# fbri_development.net
KiCad netlist of a schematic drawn in EAGLE
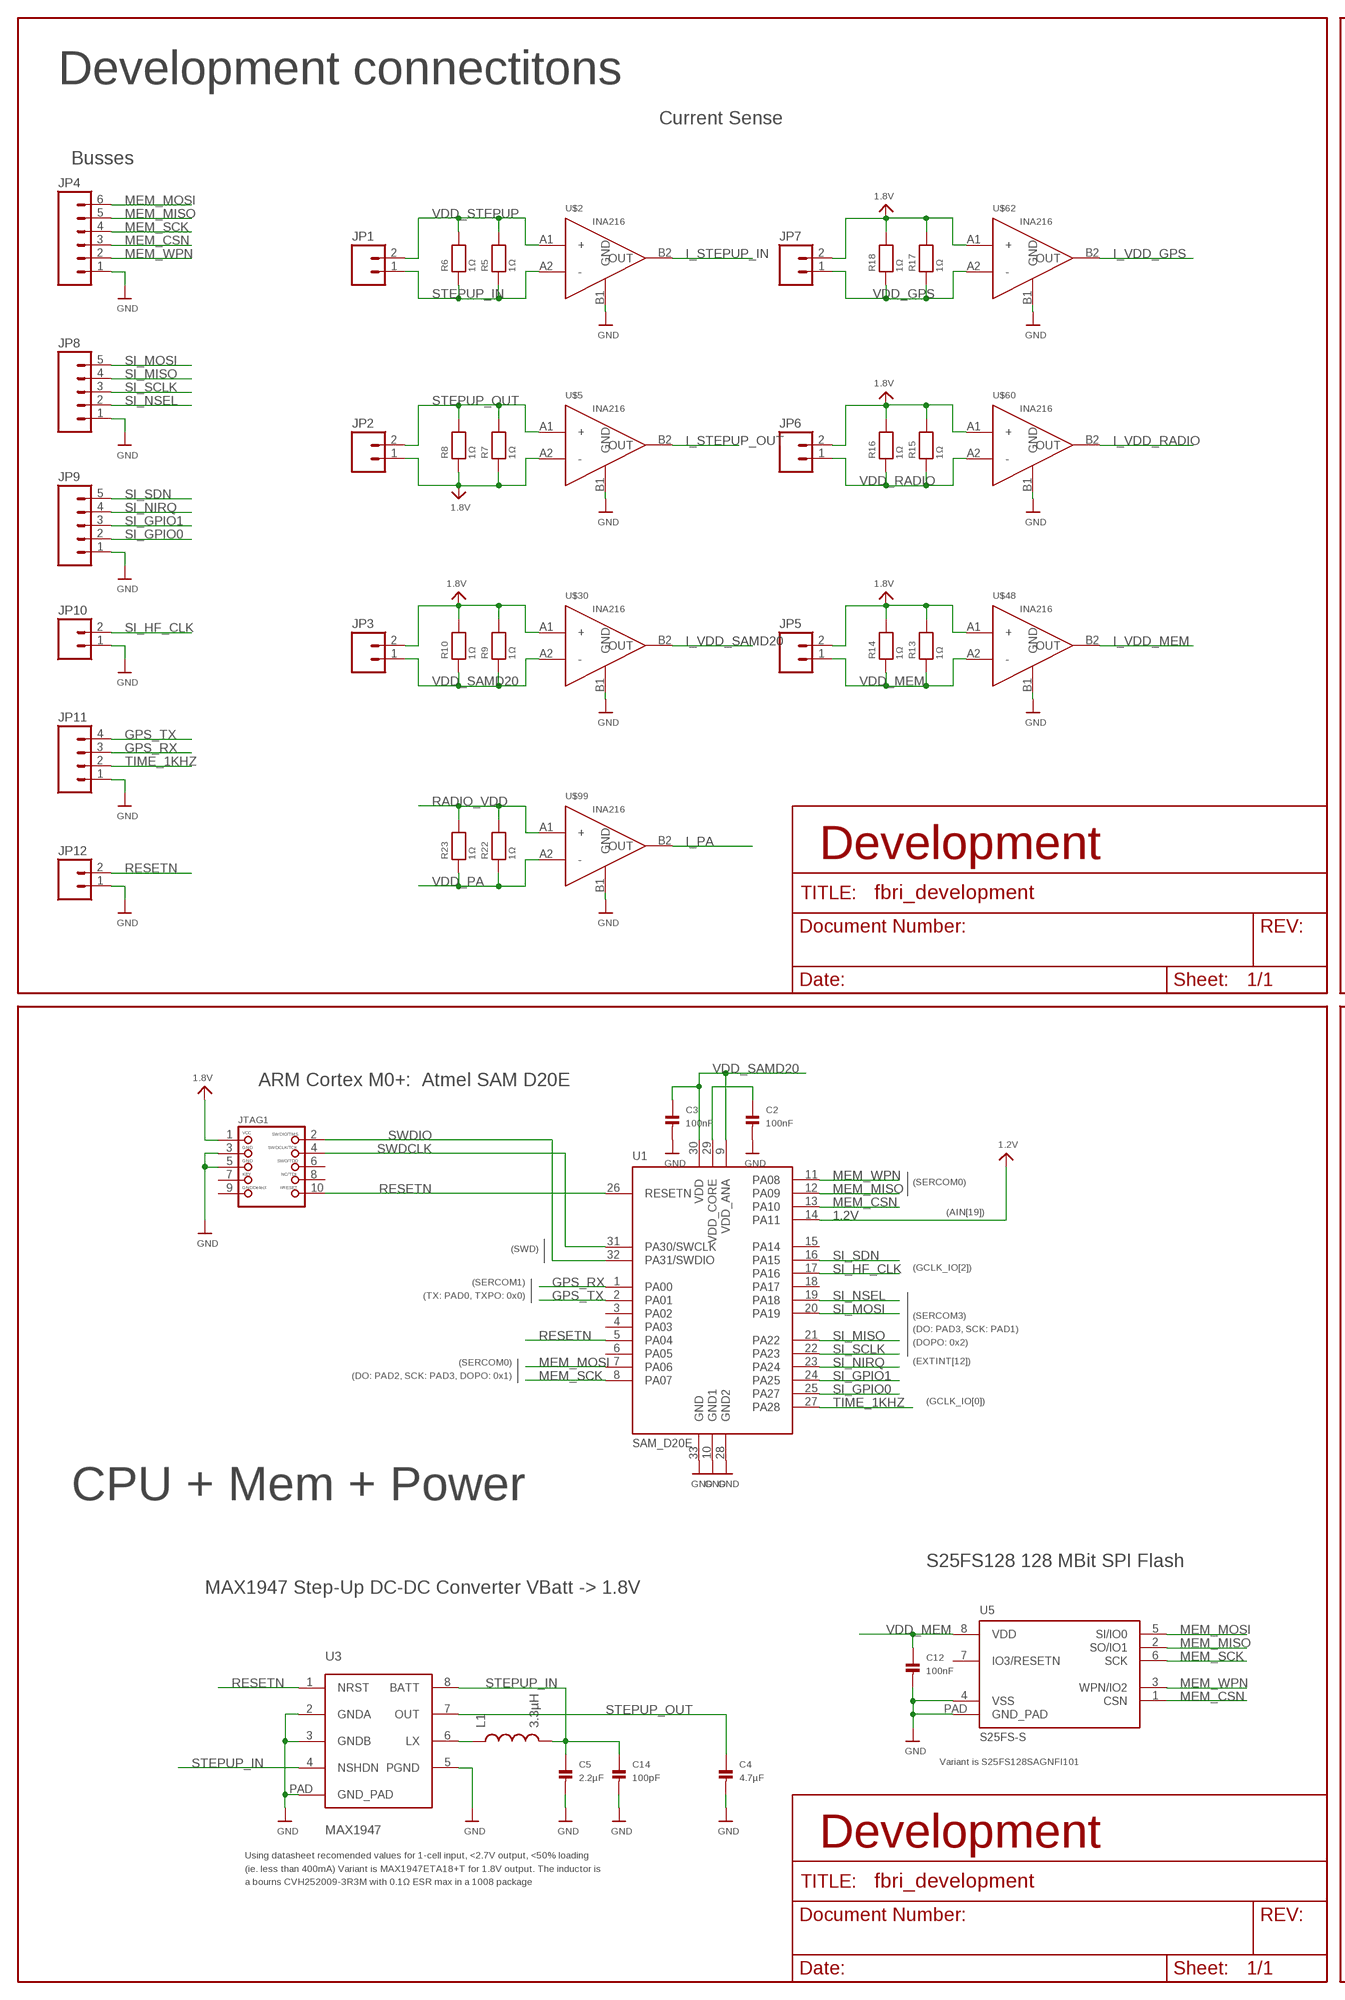
[diagram p0: schematic, sheet 1, part 1 of 2]
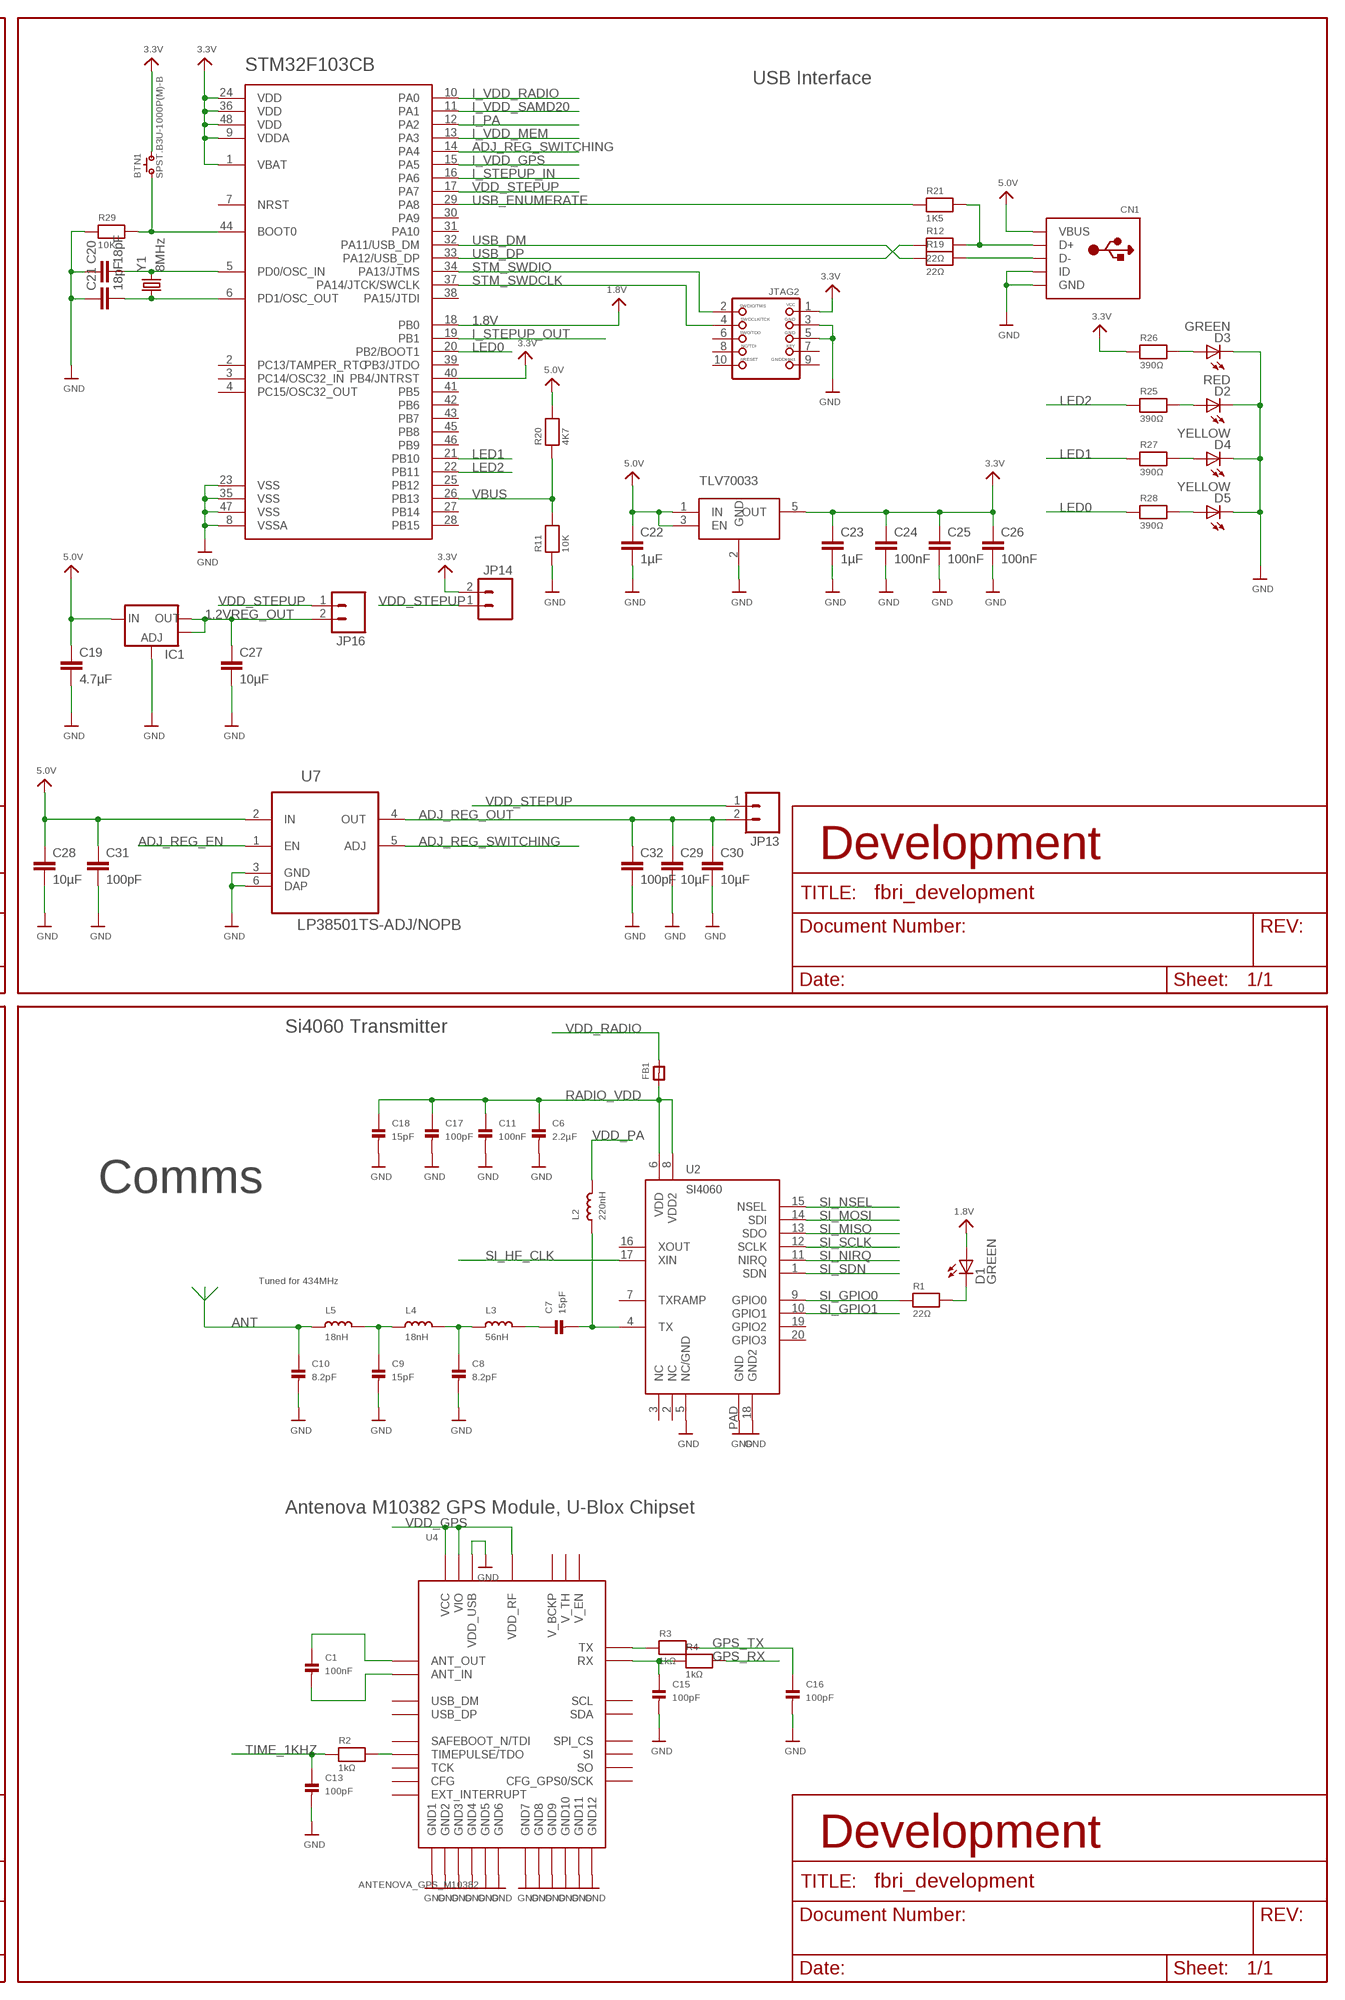
[diagram p1: schematic, sheet 1, part 2 of 2]

(export (version "E")
  (design (tool "Eeschema 10.0.6"))
  (components
    (comp (ref "BTN1")
      (value "SPST.B3U-1000P(M)-B")
      (footprint "eagle-import:B3U-1000P(M)-B")
      (libsource (lib "eagle-import") (part "SPST.B3U-1000P(M)-B"))
    )
    (comp (ref "C1")
      (value "100nF")
      (footprint "eagle-import:_0402")
      (libsource (lib "eagle-import") (part "CAP_CERAMIC_0402"))
    )
    (comp (ref "C2")
      (value "100nF")
      (footprint "eagle-import:_0402")
      (libsource (lib "eagle-import") (part "CAP_CERAMIC_0402"))
    )
    (comp (ref "C3")
      (value "100nF")
      (footprint "eagle-import:_0402")
      (libsource (lib "eagle-import") (part "CAP_CERAMIC_0402"))
    )
    (comp (ref "C4")
      (value "4.7µF")
      (footprint "eagle-import:_0402")
      (libsource (lib "eagle-import") (part "CAP_CERAMIC_0402"))
    )
    (comp (ref "C5")
      (value "2.2µF")
      (footprint "eagle-import:_0402")
      (libsource (lib "eagle-import") (part "CAP_CERAMIC_0402"))
    )
    (comp (ref "C6")
      (value "2.2µF")
      (footprint "eagle-import:_0402")
      (libsource (lib "eagle-import") (part "CAP_CERAMIC_0402"))
    )
    (comp (ref "C7")
      (value "15pF")
      (footprint "eagle-import:_0402")
      (libsource (lib "eagle-import") (part "CAP_CERAMIC_0402"))
    )
    (comp (ref "C8")
      (value "8.2pF")
      (footprint "eagle-import:_0402")
      (libsource (lib "eagle-import") (part "CAP_CERAMIC_0402"))
    )
    (comp (ref "C9")
      (value "15pF")
      (footprint "eagle-import:_0402")
      (libsource (lib "eagle-import") (part "CAP_CERAMIC_0402"))
    )
    (comp (ref "C10")
      (value "8.2pF")
      (footprint "eagle-import:_0402")
      (libsource (lib "eagle-import") (part "CAP_CERAMIC_0402"))
    )
    (comp (ref "C11")
      (value "100nF")
      (footprint "eagle-import:_0402")
      (libsource (lib "eagle-import") (part "CAP_CERAMIC_0402"))
    )
    (comp (ref "C12")
      (value "100nF")
      (footprint "eagle-import:_0402")
      (libsource (lib "eagle-import") (part "CAP_CERAMIC_0402"))
    )
    (comp (ref "C13")
      (value "100pF")
      (footprint "eagle-import:_0402")
      (libsource (lib "eagle-import") (part "CAP_CERAMIC_0402"))
    )
    (comp (ref "C14")
      (value "100pF")
      (footprint "eagle-import:_0402")
      (libsource (lib "eagle-import") (part "CAP_CERAMIC_0402"))
    )
    (comp (ref "C15")
      (value "100pF")
      (footprint "eagle-import:_0402")
      (libsource (lib "eagle-import") (part "CAP_CERAMIC_0402"))
    )
    (comp (ref "C16")
      (value "100pF")
      (footprint "eagle-import:_0402")
      (libsource (lib "eagle-import") (part "CAP_CERAMIC_0402"))
    )
    (comp (ref "C17")
      (value "100pF")
      (footprint "eagle-import:_0402")
      (libsource (lib "eagle-import") (part "CAP_CERAMIC_0402"))
    )
    (comp (ref "C18")
      (value "15pF")
      (footprint "eagle-import:_0402")
      (libsource (lib "eagle-import") (part "CAP_CERAMIC_0402"))
    )
    (comp (ref "C19")
      (value "4.7µF")
      (footprint "eagle-import:C0603K")
      (libsource (lib "eagle-import") (part "C-EUC0603K"))
    )
    (comp (ref "C20")
      (value "18pF")
      (footprint "eagle-import:C0603K")
      (libsource (lib "eagle-import") (part "C-EUC0603K"))
    )
    (comp (ref "C21")
      (value "18pF")
      (footprint "eagle-import:C0603K")
      (libsource (lib "eagle-import") (part "C-EUC0603K"))
    )
    (comp (ref "C22")
      (value "1µF")
      (footprint "eagle-import:C0603K")
      (libsource (lib "eagle-import") (part "C-EUC0603K"))
    )
    (comp (ref "C23")
      (value "1µF")
      (footprint "eagle-import:C0603K")
      (libsource (lib "eagle-import") (part "C-EUC0603K"))
    )
    (comp (ref "C24")
      (value "100nF")
      (footprint "eagle-import:C0603K")
      (libsource (lib "eagle-import") (part "C-EUC0603K"))
    )
    (comp (ref "C25")
      (value "100nF")
      (footprint "eagle-import:C0603K")
      (libsource (lib "eagle-import") (part "C-EUC0603K"))
    )
    (comp (ref "C26")
      (value "100nF")
      (footprint "eagle-import:C0603K")
      (libsource (lib "eagle-import") (part "C-EUC0603K"))
    )
    (comp (ref "C27")
      (value "10µF")
      (footprint "eagle-import:C0603K")
      (libsource (lib "eagle-import") (part "C-EUC0603K"))
    )
    (comp (ref "C28")
      (value "10µF")
      (footprint "eagle-import:C0603K")
      (libsource (lib "eagle-import") (part "C-EUC0603K"))
    )
    (comp (ref "C29")
      (value "10µF")
      (footprint "eagle-import:C0603K")
      (libsource (lib "eagle-import") (part "C-EUC0603K"))
    )
    (comp (ref "C30")
      (value "10µF")
      (footprint "eagle-import:C0603K")
      (libsource (lib "eagle-import") (part "C-EUC0603K"))
    )
    (comp (ref "C31")
      (value "100pF")
      (footprint "eagle-import:C0603K")
      (libsource (lib "eagle-import") (part "C-EUC0603K"))
    )
    (comp (ref "C32")
      (value "100pF")
      (footprint "eagle-import:C0603K")
      (libsource (lib "eagle-import") (part "C-EUC0603K"))
    )
    (comp (ref "CN1")
      (value "USBMINIB")
      (footprint "eagle-import:USB-MINIB")
      (libsource (lib "eagle-import") (part "USBMINIB"))
    )
    (comp (ref "D1")
      (value "GREEN")
      (footprint "eagle-import:CHIPLED_0603")
      (libsource (lib "eagle-import") (part "LEDCHIPLED_0603"))
    )
    (comp (ref "D2")
      (value "RED")
      (footprint "eagle-import:CHIPLED_0603")
      (libsource (lib "eagle-import") (part "LEDCHIPLED_0603"))
    )
    (comp (ref "D3")
      (value "GREEN")
      (footprint "eagle-import:CHIPLED_0603")
      (libsource (lib "eagle-import") (part "LEDCHIPLED_0603"))
    )
    (comp (ref "D4")
      (value "YELLOW")
      (footprint "eagle-import:CHIPLED_0603")
      (libsource (lib "eagle-import") (part "LEDCHIPLED_0603"))
    )
    (comp (ref "D5")
      (value "YELLOW")
      (footprint "eagle-import:CHIPLED_0603")
      (libsource (lib "eagle-import") (part "LEDCHIPLED_0603"))
    )
    (comp (ref "FB1")
      (value "FERRITE_0402")
      (footprint "eagle-import:_0402")
      (libsource (lib "eagle-import") (part "FERRITE_0402"))
    )
    (comp (ref "IC1")
      (value "V_REG_LM1117SOT223")
      (footprint "eagle-import:SOT223")
      (libsource (lib "eagle-import") (part "V_REG_LM1117SOT223"))
    )
    (comp (ref "IC3")
      (value "TLV70033DCK")
      (footprint "eagle-import:SC70-5L")
      (libsource (lib "eagle-import") (part "TLV700DCK"))
    )
    (comp (ref "JP1")
      (value "M02LOCK")
      (footprint "eagle-import:1X02_LOCK")
      (libsource (lib "eagle-import") (part "M02LOCK"))
    )
    (comp (ref "JP2")
      (value "M02LOCK")
      (footprint "eagle-import:1X02_LOCK")
      (libsource (lib "eagle-import") (part "M02LOCK"))
    )
    (comp (ref "JP3")
      (value "M02LOCK")
      (footprint "eagle-import:1X02_LOCK")
      (libsource (lib "eagle-import") (part "M02LOCK"))
    )
    (comp (ref "JP4")
      (value "M06LOCK")
      (footprint "eagle-import:1X06_LOCK")
      (libsource (lib "eagle-import") (part "M06LOCK"))
    )
    (comp (ref "JP5")
      (value "M02LOCK")
      (footprint "eagle-import:1X02_LOCK")
      (libsource (lib "eagle-import") (part "M02LOCK"))
    )
    (comp (ref "JP6")
      (value "M02LOCK")
      (footprint "eagle-import:1X02_LOCK")
      (libsource (lib "eagle-import") (part "M02LOCK"))
    )
    (comp (ref "JP7")
      (value "M02LOCK")
      (footprint "eagle-import:1X02_LOCK")
      (libsource (lib "eagle-import") (part "M02LOCK"))
    )
    (comp (ref "JP8")
      (value "M05LOCK")
      (footprint "eagle-import:1X05_LOCK")
      (libsource (lib "eagle-import") (part "M05LOCK"))
    )
    (comp (ref "JP9")
      (value "M05LOCK")
      (footprint "eagle-import:1X05_LOCK")
      (libsource (lib "eagle-import") (part "M05LOCK"))
    )
    (comp (ref "JP10")
      (value "M02LOCK")
      (footprint "eagle-import:1X02_LOCK")
      (libsource (lib "eagle-import") (part "M02LOCK"))
    )
    (comp (ref "JP11")
      (value "M04LOCK")
      (footprint "eagle-import:1X04_LOCK")
      (libsource (lib "eagle-import") (part "M04LOCK"))
    )
    (comp (ref "JP12")
      (value "M02LOCK")
      (footprint "eagle-import:1X02_LOCK")
      (libsource (lib "eagle-import") (part "M02LOCK"))
    )
    (comp (ref "JP13")
      (value "M02LOCK")
      (footprint "eagle-import:1X02_LOCK")
      (libsource (lib "eagle-import") (part "M02LOCK"))
    )
    (comp (ref "JP14")
      (value "M02LOCK")
      (footprint "eagle-import:1X02_LOCK")
      (libsource (lib "eagle-import") (part "M02LOCK"))
    )
    (comp (ref "JP16")
      (value "M02LOCK")
      (footprint "eagle-import:1X02_LOCK")
      (libsource (lib "eagle-import") (part "M02LOCK"))
    )
    (comp (ref "JTAG1")
      (value "JTAG-CORTEXM3SMT")
      (footprint "eagle-import:2X05_1.27MM_SMT")
      (libsource (lib "eagle-import") (part "JTAG-CORTEXM3SMT"))
    )
    (comp (ref "JTAG2")
      (value "JTAG-CORTEXM3SMT")
      (footprint "eagle-import:2X05_1.27MM_SMT")
      (libsource (lib "eagle-import") (part "JTAG-CORTEXM3SMT"))
    )
    (comp (ref "L1")
      (value "3.3µH")
      (footprint "eagle-import:1007")
      (libsource (lib "eagle-import") (part "INDUCTOR1007"))
    )
    (comp (ref "L2")
      (value "220nH")
      (footprint "eagle-import:_0402")
      (libsource (lib "eagle-import") (part "INDUCTOR_0402"))
    )
    (comp (ref "L3")
      (value "56nH")
      (footprint "eagle-import:_0402")
      (libsource (lib "eagle-import") (part "INDUCTOR_0402"))
    )
    (comp (ref "L4")
      (value "18nH")
      (footprint "eagle-import:_0402")
      (libsource (lib "eagle-import") (part "INDUCTOR_0402"))
    )
    (comp (ref "L5")
      (value "18nH")
      (footprint "eagle-import:_0402")
      (libsource (lib "eagle-import") (part "INDUCTOR_0402"))
    )
    (comp (ref "R1")
      (value "22Ω")
      (footprint "eagle-import:_0402")
      (libsource (lib "eagle-import") (part "RESISTOR_0402"))
    )
    (comp (ref "R2")
      (value "1kΩ")
      (footprint "eagle-import:_0402")
      (libsource (lib "eagle-import") (part "RESISTOR_0402"))
    )
    (comp (ref "R3")
      (value "1kΩ")
      (footprint "eagle-import:_0402")
      (libsource (lib "eagle-import") (part "RESISTOR_0402"))
    )
    (comp (ref "R4")
      (value "1kΩ")
      (footprint "eagle-import:_0402")
      (libsource (lib "eagle-import") (part "RESISTOR_0402"))
    )
    (comp (ref "R5")
      (value "1Ω")
      (footprint "eagle-import:_0402")
      (libsource (lib "eagle-import") (part "RESISTOR_0402"))
    )
    (comp (ref "R6")
      (value "1Ω")
      (footprint "eagle-import:_0402")
      (libsource (lib "eagle-import") (part "RESISTOR_0402"))
    )
    (comp (ref "R7")
      (value "1Ω")
      (footprint "eagle-import:_0402")
      (libsource (lib "eagle-import") (part "RESISTOR_0402"))
    )
    (comp (ref "R8")
      (value "1Ω")
      (footprint "eagle-import:_0402")
      (libsource (lib "eagle-import") (part "RESISTOR_0402"))
    )
    (comp (ref "R9")
      (value "1Ω")
      (footprint "eagle-import:_0402")
      (libsource (lib "eagle-import") (part "RESISTOR_0402"))
    )
    (comp (ref "R10")
      (value "1Ω")
      (footprint "eagle-import:_0402")
      (libsource (lib "eagle-import") (part "RESISTOR_0402"))
    )
    (comp (ref "R11")
      (value "10K")
      (footprint "eagle-import:0603-MINI")
      (libsource (lib "eagle-import") (part "RESISTOR0603MINI"))
    )
    (comp (ref "R12")
      (value "22Ω")
      (footprint "eagle-import:0603-MINI")
      (libsource (lib "eagle-import") (part "RESISTOR0603MINI"))
    )
    (comp (ref "R13")
      (value "1Ω")
      (footprint "eagle-import:_0402")
      (libsource (lib "eagle-import") (part "RESISTOR_0402"))
    )
    (comp (ref "R14")
      (value "1Ω")
      (footprint "eagle-import:_0402")
      (libsource (lib "eagle-import") (part "RESISTOR_0402"))
    )
    (comp (ref "R15")
      (value "1Ω")
      (footprint "eagle-import:_0402")
      (libsource (lib "eagle-import") (part "RESISTOR_0402"))
    )
    (comp (ref "R16")
      (value "1Ω")
      (footprint "eagle-import:_0402")
      (libsource (lib "eagle-import") (part "RESISTOR_0402"))
    )
    (comp (ref "R17")
      (value "1Ω")
      (footprint "eagle-import:_0402")
      (libsource (lib "eagle-import") (part "RESISTOR_0402"))
    )
    (comp (ref "R18")
      (value "1Ω")
      (footprint "eagle-import:_0402")
      (libsource (lib "eagle-import") (part "RESISTOR_0402"))
    )
    (comp (ref "R19")
      (value "22Ω")
      (footprint "eagle-import:0603-MINI")
      (libsource (lib "eagle-import") (part "RESISTOR0603MINI"))
    )
    (comp (ref "R20")
      (value "4K7")
      (footprint "eagle-import:0603-MINI")
      (libsource (lib "eagle-import") (part "RESISTOR0603MINI"))
    )
    (comp (ref "R21")
      (value "1K5")
      (footprint "eagle-import:0603-MINI")
      (libsource (lib "eagle-import") (part "RESISTOR0603MINI"))
    )
    (comp (ref "R22")
      (value "1Ω")
      (footprint "eagle-import:_0402")
      (libsource (lib "eagle-import") (part "RESISTOR_0402"))
    )
    (comp (ref "R23")
      (value "1Ω")
      (footprint "eagle-import:_0402")
      (libsource (lib "eagle-import") (part "RESISTOR_0402"))
    )
    (comp (ref "R25")
      (value "390Ω")
      (footprint "eagle-import:0603-MINI")
      (libsource (lib "eagle-import") (part "RESISTOR0603MINI"))
    )
    (comp (ref "R26")
      (value "390Ω")
      (footprint "eagle-import:0603-MINI")
      (libsource (lib "eagle-import") (part "RESISTOR0603MINI"))
    )
    (comp (ref "R27")
      (value "390Ω")
      (footprint "eagle-import:0603-MINI")
      (libsource (lib "eagle-import") (part "RESISTOR0603MINI"))
    )
    (comp (ref "R28")
      (value "390Ω")
      (footprint "eagle-import:0603-MINI")
      (libsource (lib "eagle-import") (part "RESISTOR0603MINI"))
    )
    (comp (ref "R29")
      (value "10K")
      (footprint "eagle-import:0603-MINI")
      (libsource (lib "eagle-import") (part "RESISTOR0603MINI"))
    )
    (comp (ref "U$2")
      (value "INA216")
      (footprint "eagle-import:WCSP-4")
      (libsource (lib "eagle-import") (part "INA216"))
    )
    (comp (ref "U$5")
      (value "INA216")
      (footprint "eagle-import:WCSP-4")
      (libsource (lib "eagle-import") (part "INA216"))
    )
    (comp (ref "U$30")
      (value "INA216")
      (footprint "eagle-import:WCSP-4")
      (libsource (lib "eagle-import") (part "INA216"))
    )
    (comp (ref "U$48")
      (value "INA216")
      (footprint "eagle-import:WCSP-4")
      (libsource (lib "eagle-import") (part "INA216"))
    )
    (comp (ref "U$60")
      (value "INA216")
      (footprint "eagle-import:WCSP-4")
      (libsource (lib "eagle-import") (part "INA216"))
    )
    (comp (ref "U$62")
      (value "INA216")
      (footprint "eagle-import:WCSP-4")
      (libsource (lib "eagle-import") (part "INA216"))
    )
    (comp (ref "U$99")
      (value "INA216")
      (footprint "eagle-import:WCSP-4")
      (libsource (lib "eagle-import") (part "INA216"))
    )
    (comp (ref "U1")
      (value "SAM_D20E")
      (footprint "eagle-import:QFN32_5MM")
      (libsource (lib "eagle-import") (part "SAM_D20E"))
    )
    (comp (ref "U2")
      (value "SI4060")
      (footprint "eagle-import:QFN20")
      (libsource (lib "eagle-import") (part "SI4060"))
    )
    (comp (ref "U3")
      (value "MAX1947")
      (footprint "eagle-import:TDFN8")
      (libsource (lib "eagle-import") (part "MAX1947"))
    )
    (comp (ref "U4")
      (value "ANTENOVA_GPS_M10382")
      (footprint "eagle-import:ANTENOVA_GPS_M10382")
      (libsource (lib "eagle-import") (part "ANTENOVA_GPS_M10382"))
    )
    (comp (ref "U5")
      (value "S25FS-S")
      (footprint "eagle-import:WSON8")
      (libsource (lib "eagle-import") (part "S25FS-S"))
    )
    (comp (ref "U6")
      (value "STM32F_48PIN")
      (footprint "eagle-import:TQFP48")
      (libsource (lib "eagle-import") (part "STM32F_48PIN"))
    )
    (comp (ref "U7")
      (value "LP38501TS-ADJ/NOPB")
      (footprint "eagle-import:TO170P1435X457-6N")
      (libsource (lib "eagle-import") (part "LP38501TS-ADJ/NOPB"))
    )
    (comp (ref "Y1")
      (value "8MHz")
      (footprint "eagle-import:CRYSTAL-SMD-5X3")
      (libsource (lib "eagle-import") (part "CRYSTAL5X3"))
    )
  )
  (nets
    (net (code "1") (name "/1.2VREG_OUT") (class "Default")
      (node (ref "C27") (pin "1") (pinfunction "1_1") (pintype "passive"))
      (node (ref "IC1") (pin "2") (pinfunction "OUT_2") (pintype "output"))
      (node (ref "IC1") (pin "4") (pinfunction "OUT_4") (pintype "output"))
      (node (ref "JP16") (pin "2") (pinfunction "2_2") (pintype "passive"))
    )
    (net (code "2") (name "/ADJ_REG_EN") (class "Default")
      (node (ref "U7") (pin "1") (pinfunction "EN_1") (pintype "input"))
    )
    (net (code "3") (name "/ADJ_REG_OUT") (class "Default")
      (node (ref "C29") (pin "1") (pinfunction "1_1") (pintype "passive"))
      (node (ref "C30") (pin "1") (pinfunction "1_1") (pintype "passive"))
      (node (ref "C32") (pin "1") (pinfunction "1_1") (pintype "passive"))
      (node (ref "JP13") (pin "2") (pinfunction "2_2") (pintype "passive"))
      (node (ref "U7") (pin "4") (pinfunction "OUT_4") (pintype "output"))
    )
    (net (code "4") (name "/ADJ_REG_SWITCHING") (class "Default")
      (node (ref "U6") (pin "14") (pinfunction "PA4_14") (pintype "bidirectional"))
      (node (ref "U7") (pin "5") (pinfunction "ADJ_5") (pintype "input"))
    )
    (net (code "5") (name "/ANT") (class "Default")
      (node (ref "C10") (pin "1") (pinfunction "P$1_1") (pintype "passive"))
      (node (ref "L5") (pin "1") (pinfunction "1_1") (pintype "passive"))
    )
    (net (code "6") (name "/GPS_RX") (class "Default")
      (node (ref "JP11") (pin "3") (pinfunction "3_3") (pintype "passive"))
      (node (ref "R4") (pin "2") (pinfunction "2_2") (pintype "passive"))
      (node (ref "U1") (pin "1") (pinfunction "PA00_1") (pintype "bidirectional"))
    )
    (net (code "7") (name "/GPS_TX") (class "Default")
      (node (ref "C16") (pin "1") (pinfunction "P$1_1") (pintype "passive"))
      (node (ref "JP11") (pin "4") (pinfunction "4_4") (pintype "passive"))
      (node (ref "R3") (pin "2") (pinfunction "2_2") (pintype "passive"))
      (node (ref "U1") (pin "2") (pinfunction "PA01_2") (pintype "bidirectional"))
    )
    (net (code "8") (name "/I_PA") (class "Default")
      (node (ref "U$99") (pin "B2") (pinfunction "OUT_B2") (pintype "bidirectional"))
      (node (ref "U6") (pin "12") (pinfunction "PA2_12") (pintype "bidirectional"))
    )
    (net (code "9") (name "/I_STEPUP_IN") (class "Default")
      (node (ref "U$2") (pin "B2") (pinfunction "OUT_B2") (pintype "bidirectional"))
      (node (ref "U6") (pin "16") (pinfunction "PA6_16") (pintype "bidirectional"))
    )
    (net (code "10") (name "/I_STEPUP_OUT") (class "Default")
      (node (ref "U$5") (pin "B2") (pinfunction "OUT_B2") (pintype "bidirectional"))
      (node (ref "U6") (pin "19") (pinfunction "PB1_19") (pintype "bidirectional"))
    )
    (net (code "11") (name "/I_VDD_GPS") (class "Default")
      (node (ref "U$62") (pin "B2") (pinfunction "OUT_B2") (pintype "bidirectional"))
      (node (ref "U6") (pin "15") (pinfunction "PA5_15") (pintype "bidirectional"))
    )
    (net (code "12") (name "/I_VDD_MEM") (class "Default")
      (node (ref "U$48") (pin "B2") (pinfunction "OUT_B2") (pintype "bidirectional"))
      (node (ref "U6") (pin "13") (pinfunction "PA3_13") (pintype "bidirectional"))
    )
    (net (code "13") (name "/I_VDD_RADIO") (class "Default")
      (node (ref "U$60") (pin "B2") (pinfunction "OUT_B2") (pintype "bidirectional"))
      (node (ref "U6") (pin "10") (pinfunction "PA0_10") (pintype "bidirectional"))
    )
    (net (code "14") (name "/I_VDD_SAMD20") (class "Default")
      (node (ref "U$30") (pin "B2") (pinfunction "OUT_B2") (pintype "bidirectional"))
      (node (ref "U6") (pin "11") (pinfunction "PA1_11") (pintype "bidirectional"))
    )
    (net (code "15") (name "/LED0") (class "Default")
      (node (ref "R28") (pin "1") (pinfunction "1_1") (pintype "passive"))
      (node (ref "U6") (pin "20") (pinfunction "PB2/BOOT1_20") (pintype "bidirectional"))
    )
    (net (code "16") (name "/LED1") (class "Default")
      (node (ref "R27") (pin "1") (pinfunction "1_1") (pintype "passive"))
      (node (ref "U6") (pin "21") (pinfunction "PB10_21") (pintype "bidirectional"))
    )
    (net (code "17") (name "/LED2") (class "Default")
      (node (ref "R25") (pin "1") (pinfunction "1_1") (pintype "passive"))
      (node (ref "U6") (pin "22") (pinfunction "PB11_22") (pintype "bidirectional"))
    )
    (net (code "18") (name "/MEM_CSN") (class "Default")
      (node (ref "JP4") (pin "3") (pinfunction "3_3") (pintype "passive"))
      (node (ref "U1") (pin "13") (pinfunction "PA10_13") (pintype "bidirectional"))
      (node (ref "U5") (pin "1") (pinfunction "CSN_1") (pintype "input"))
    )
    (net (code "19") (name "/MEM_MISO") (class "Default")
      (node (ref "JP4") (pin "5") (pinfunction "5_5") (pintype "passive"))
      (node (ref "U1") (pin "12") (pinfunction "PA09_12") (pintype "bidirectional"))
      (node (ref "U5") (pin "2") (pinfunction "SO/IO1_2") (pintype "output"))
    )
    (net (code "20") (name "/MEM_MOSI") (class "Default")
      (node (ref "JP4") (pin "6") (pinfunction "6_6") (pintype "passive"))
      (node (ref "U1") (pin "7") (pinfunction "PA06_7") (pintype "bidirectional"))
      (node (ref "U5") (pin "5") (pinfunction "SI/IO0_5") (pintype "bidirectional"))
    )
    (net (code "21") (name "/MEM_SCK") (class "Default")
      (node (ref "JP4") (pin "4") (pinfunction "4_4") (pintype "passive"))
      (node (ref "U1") (pin "8") (pinfunction "PA07_8") (pintype "bidirectional"))
      (node (ref "U5") (pin "6") (pinfunction "SCK_6") (pintype "input"))
    )
    (net (code "22") (name "/MEM_WPN") (class "Default")
      (node (ref "JP4") (pin "2") (pinfunction "2_2") (pintype "passive"))
      (node (ref "U1") (pin "11") (pinfunction "PA08_11") (pintype "bidirectional"))
      (node (ref "U5") (pin "3") (pinfunction "WPN/IO2_3") (pintype "output"))
    )
    (net (code "23") (name "/RADIO_VDD") (class "Default")
      (node (ref "C11") (pin "1") (pinfunction "P$1_1") (pintype "passive"))
      (node (ref "C17") (pin "1") (pinfunction "P$1_1") (pintype "passive"))
      (node (ref "C18") (pin "1") (pinfunction "P$1_1") (pintype "passive"))
      (node (ref "C6") (pin "1") (pinfunction "P$1_1") (pintype "passive"))
      (node (ref "FB1") (pin "1") (pinfunction "P$1_1") (pintype "passive"))
      (node (ref "R22") (pin "2") (pinfunction "2_2") (pintype "passive"))
      (node (ref "R23") (pin "2") (pinfunction "2_2") (pintype "passive"))
      (node (ref "U$99") (pin "A1") (pinfunction "+_A1") (pintype "bidirectional"))
      (node (ref "U2") (pin "6") (pinfunction "VDD_6") (pintype "power_in"))
      (node (ref "U2") (pin "8") (pinfunction "VDD2_8") (pintype "power_in"))
    )
    (net (code "24") (name "/RESETN") (class "Default")
      (node (ref "JP12") (pin "2") (pinfunction "2_2") (pintype "passive"))
      (node (ref "JTAG1") (pin "10") (pinfunction "10_10") (pintype "passive"))
      (node (ref "U1") (pin "26") (pinfunction "RESETN_26") (pintype "input"))
      (node (ref "U1") (pin "5") (pinfunction "PA04_5") (pintype "bidirectional"))
      (node (ref "U3") (pin "1") (pinfunction "NRST_1") (pintype "bidirectional"))
    )
    (net (code "25") (name "/SI_GPIO0") (class "Default")
      (node (ref "JP9") (pin "2") (pinfunction "2_2") (pintype "passive"))
      (node (ref "R1") (pin "1") (pinfunction "1_1") (pintype "passive"))
      (node (ref "U1") (pin "25") (pinfunction "PA27_25") (pintype "bidirectional"))
      (node (ref "U2") (pin "9") (pinfunction "GPIO0_9") (pintype "bidirectional"))
    )
    (net (code "26") (name "/SI_GPIO1") (class "Default")
      (node (ref "JP9") (pin "3") (pinfunction "3_3") (pintype "passive"))
      (node (ref "U1") (pin "24") (pinfunction "PA25_24") (pintype "bidirectional"))
      (node (ref "U2") (pin "10") (pinfunction "GPIO1_10") (pintype "bidirectional"))
    )
    (net (code "27") (name "/SI_HF_CLK") (class "Default")
      (node (ref "JP10") (pin "2") (pinfunction "2_2") (pintype "passive"))
      (node (ref "U1") (pin "17") (pinfunction "PA16_17") (pintype "bidirectional"))
      (node (ref "U2") (pin "17") (pinfunction "XIN_17") (pintype "input"))
    )
    (net (code "28") (name "/SI_MISO") (class "Default")
      (node (ref "JP8") (pin "4") (pinfunction "4_4") (pintype "passive"))
      (node (ref "U1") (pin "21") (pinfunction "PA22_21") (pintype "bidirectional"))
      (node (ref "U2") (pin "13") (pinfunction "SDO_13") (pintype "output"))
    )
    (net (code "29") (name "/SI_MOSI") (class "Default")
      (node (ref "JP8") (pin "5") (pinfunction "5_5") (pintype "passive"))
      (node (ref "U1") (pin "20") (pinfunction "PA19_20") (pintype "bidirectional"))
      (node (ref "U2") (pin "14") (pinfunction "SDI_14") (pintype "bidirectional"))
    )
    (net (code "30") (name "/SI_NIRQ") (class "Default")
      (node (ref "JP9") (pin "4") (pinfunction "4_4") (pintype "passive"))
      (node (ref "U1") (pin "23") (pinfunction "PA24_23") (pintype "bidirectional"))
      (node (ref "U2") (pin "11") (pinfunction "NIRQ_11") (pintype "output"))
    )
    (net (code "31") (name "/SI_NSEL") (class "Default")
      (node (ref "JP8") (pin "2") (pinfunction "2_2") (pintype "passive"))
      (node (ref "U1") (pin "19") (pinfunction "PA18_19") (pintype "bidirectional"))
      (node (ref "U2") (pin "15") (pinfunction "NSEL_15") (pintype "input"))
    )
    (net (code "32") (name "/SI_SCLK") (class "Default")
      (node (ref "JP8") (pin "3") (pinfunction "3_3") (pintype "passive"))
      (node (ref "U1") (pin "22") (pinfunction "PA23_22") (pintype "bidirectional"))
      (node (ref "U2") (pin "12") (pinfunction "SCLK_12") (pintype "input"))
    )
    (net (code "33") (name "/SI_SDN") (class "Default")
      (node (ref "JP9") (pin "5") (pinfunction "5_5") (pintype "passive"))
      (node (ref "U1") (pin "16") (pinfunction "PA15_16") (pintype "bidirectional"))
      (node (ref "U2") (pin "1") (pinfunction "SDN_1") (pintype "input"))
    )
    (net (code "34") (name "/STEPUP_IN") (class "Default")
      (node (ref "C14") (pin "1") (pinfunction "P$1_1") (pintype "passive"))
      (node (ref "C5") (pin "1") (pinfunction "P$1_1") (pintype "passive"))
      (node (ref "JP1") (pin "1") (pinfunction "1_1") (pintype "passive"))
      (node (ref "L1") (pin "2") (pinfunction "2_2") (pintype "passive"))
      (node (ref "R5") (pin "1") (pinfunction "1_1") (pintype "passive"))
      (node (ref "R6") (pin "1") (pinfunction "1_1") (pintype "passive"))
      (node (ref "U$2") (pin "A2") (pinfunction "-_A2") (pintype "bidirectional"))
      (node (ref "U3") (pin "4") (pinfunction "NSHDN_4") (pintype "bidirectional"))
      (node (ref "U3") (pin "8") (pinfunction "BATT_8") (pintype "bidirectional"))
    )
    (net (code "35") (name "/STEPUP_OUT") (class "Default")
      (node (ref "C4") (pin "1") (pinfunction "P$1_1") (pintype "passive"))
      (node (ref "JP2") (pin "2") (pinfunction "2_2") (pintype "passive"))
      (node (ref "R7") (pin "2") (pinfunction "2_2") (pintype "passive"))
      (node (ref "R8") (pin "2") (pinfunction "2_2") (pintype "passive"))
      (node (ref "U$5") (pin "A1") (pinfunction "+_A1") (pintype "bidirectional"))
      (node (ref "U3") (pin "7") (pinfunction "OUT_7") (pintype "bidirectional"))
    )
    (net (code "36") (name "/STM_SWDCLK") (class "Default")
      (node (ref "JTAG2") (pin "4") (pinfunction "4_4") (pintype "passive"))
      (node (ref "U6") (pin "37") (pinfunction "PA14/JTCK/SWCLK_37") (pintype "bidirectional"))
    )
    (net (code "37") (name "/STM_SWDIO") (class "Default")
      (node (ref "JTAG2") (pin "2") (pinfunction "2_2") (pintype "passive"))
      (node (ref "U6") (pin "34") (pinfunction "PA13/JTMS_34") (pintype "bidirectional"))
    )
    (net (code "38") (name "/SWDCLK") (class "Default")
      (node (ref "JTAG1") (pin "4") (pinfunction "4_4") (pintype "passive"))
      (node (ref "U1") (pin "31") (pinfunction "PA30/SWCLK_31") (pintype "bidirectional"))
    )
    (net (code "39") (name "/SWDIO") (class "Default")
      (node (ref "JTAG1") (pin "2") (pinfunction "2_2") (pintype "passive"))
      (node (ref "U1") (pin "32") (pinfunction "PA31/SWDIO_32") (pintype "bidirectional"))
    )
    (net (code "40") (name "/TIME_1KHZ") (class "Default")
      (node (ref "C13") (pin "1") (pinfunction "P$1_1") (pintype "passive"))
      (node (ref "JP11") (pin "2") (pinfunction "2_2") (pintype "passive"))
      (node (ref "R2") (pin "1") (pinfunction "1_1") (pintype "passive"))
      (node (ref "U1") (pin "27") (pinfunction "PA28_27") (pintype "bidirectional"))
    )
    (net (code "41") (name "/USB_DM") (class "Default")
      (node (ref "R19") (pin "1") (pinfunction "1_1") (pintype "passive"))
      (node (ref "U6") (pin "32") (pinfunction "PA11/USB_DM_32") (pintype "bidirectional"))
    )
    (net (code "42") (name "/USB_DP") (class "Default")
      (node (ref "R12") (pin "1") (pinfunction "1_1") (pintype "passive"))
      (node (ref "U6") (pin "33") (pinfunction "PA12/USB_DP_33") (pintype "bidirectional"))
    )
    (net (code "43") (name "/USB_ENUMERATE") (class "Default")
      (node (ref "R21") (pin "1") (pinfunction "1_1") (pintype "passive"))
      (node (ref "U6") (pin "29") (pinfunction "PA8_29") (pintype "bidirectional"))
    )
    (net (code "44") (name "/VBUS") (class "Default")
      (node (ref "R11") (pin "2") (pinfunction "2_2") (pintype "passive"))
      (node (ref "R20") (pin "1") (pinfunction "1_1") (pintype "passive"))
      (node (ref "U6") (pin "26") (pinfunction "PB13_26") (pintype "bidirectional"))
    )
    (net (code "45") (name "/VDD_GPS") (class "Default")
      (node (ref "JP7") (pin "1") (pinfunction "1_1") (pintype "passive"))
      (node (ref "R17") (pin "1") (pinfunction "1_1") (pintype "passive"))
      (node (ref "R18") (pin "1") (pinfunction "1_1") (pintype "passive"))
      (node (ref "U$62") (pin "A2") (pinfunction "-_A2") (pintype "bidirectional"))
      (node (ref "U4") (pin "25_VDD_RF") (pinfunction "VDD_RF_25_VDD_RF") (pintype "power_in"))
      (node (ref "U4") (pin "27_VCC") (pinfunction "VCC_27_VCC") (pintype "power_in"))
      (node (ref "U4") (pin "5_VIO") (pinfunction "VIO_5_VIO") (pintype "bidirectional"))
    )
    (net (code "46") (name "/VDD_MEM") (class "Default")
      (node (ref "C12") (pin "1") (pinfunction "P$1_1") (pintype "passive"))
      (node (ref "JP5") (pin "1") (pinfunction "1_1") (pintype "passive"))
      (node (ref "R13") (pin "1") (pinfunction "1_1") (pintype "passive"))
      (node (ref "R14") (pin "1") (pinfunction "1_1") (pintype "passive"))
      (node (ref "U$48") (pin "A2") (pinfunction "-_A2") (pintype "bidirectional"))
      (node (ref "U5") (pin "8") (pinfunction "VDD_8") (pintype "power_in"))
    )
    (net (code "47") (name "/VDD_PA") (class "Default")
      (node (ref "L2") (pin "2") (pinfunction "2_2") (pintype "passive"))
      (node (ref "R22") (pin "1") (pinfunction "1_1") (pintype "passive"))
      (node (ref "R23") (pin "1") (pinfunction "1_1") (pintype "passive"))
      (node (ref "U$99") (pin "A2") (pinfunction "-_A2") (pintype "bidirectional"))
    )
    (net (code "48") (name "/VDD_RADIO") (class "Default")
      (node (ref "FB1") (pin "2") (pinfunction "P$2_2") (pintype "passive"))
      (node (ref "JP6") (pin "1") (pinfunction "1_1") (pintype "passive"))
      (node (ref "R15") (pin "1") (pinfunction "1_1") (pintype "passive"))
      (node (ref "R16") (pin "1") (pinfunction "1_1") (pintype "passive"))
      (node (ref "U$60") (pin "A2") (pinfunction "-_A2") (pintype "bidirectional"))
    )
    (net (code "49") (name "/VDD_SAMD20") (class "Default")
      (node (ref "C3") (pin "1") (pinfunction "P$1_1") (pintype "passive"))
      (node (ref "JP3") (pin "1") (pinfunction "1_1") (pintype "passive"))
      (node (ref "R10") (pin "1") (pinfunction "1_1") (pintype "passive"))
      (node (ref "R9") (pin "1") (pinfunction "1_1") (pintype "passive"))
      (node (ref "U$30") (pin "A2") (pinfunction "-_A2") (pintype "bidirectional"))
      (node (ref "U1") (pin "30") (pinfunction "VDD_30") (pintype "power_in"))
      (node (ref "U1") (pin "9") (pinfunction "VDD_ANA_9") (pintype "power_in"))
    )
    (net (code "50") (name "/VDD_STEPUP") (class "Default")
      (node (ref "JP1") (pin "2") (pinfunction "2_2") (pintype "passive"))
      (node (ref "JP13") (pin "1") (pinfunction "1_1") (pintype "passive"))
      (node (ref "JP14") (pin "1") (pinfunction "1_1") (pintype "passive"))
      (node (ref "JP16") (pin "1") (pinfunction "1_1") (pintype "passive"))
      (node (ref "R5") (pin "2") (pinfunction "2_2") (pintype "passive"))
      (node (ref "R6") (pin "2") (pinfunction "2_2") (pintype "passive"))
      (node (ref "U$2") (pin "A1") (pinfunction "+_A1") (pintype "bidirectional"))
      (node (ref "U6") (pin "17") (pinfunction "PA7_17") (pintype "bidirectional"))
    )
    (net (code "51") (name "1.2V") (class "Default")
      (node (ref "U1") (pin "14") (pinfunction "PA11_14") (pintype "bidirectional"))
    )
    (net (code "52") (name "1.8V") (class "Default")
      (node (ref "D1") (pin "A") (pinfunction "A_A") (pintype "passive"))
      (node (ref "JP2") (pin "1") (pinfunction "1_1") (pintype "passive"))
      (node (ref "JP3") (pin "2") (pinfunction "2_2") (pintype "passive"))
      (node (ref "JP5") (pin "2") (pinfunction "2_2") (pintype "passive"))
      (node (ref "JP6") (pin "2") (pinfunction "2_2") (pintype "passive"))
      (node (ref "JP7") (pin "2") (pinfunction "2_2") (pintype "passive"))
      (node (ref "JTAG1") (pin "1") (pinfunction "1_1") (pintype "passive"))
      (node (ref "R10") (pin "2") (pinfunction "2_2") (pintype "passive"))
      (node (ref "R13") (pin "2") (pinfunction "2_2") (pintype "passive"))
      (node (ref "R14") (pin "2") (pinfunction "2_2") (pintype "passive"))
      (node (ref "R15") (pin "2") (pinfunction "2_2") (pintype "passive"))
      (node (ref "R16") (pin "2") (pinfunction "2_2") (pintype "passive"))
      (node (ref "R17") (pin "2") (pinfunction "2_2") (pintype "passive"))
      (node (ref "R18") (pin "2") (pinfunction "2_2") (pintype "passive"))
      (node (ref "R7") (pin "1") (pinfunction "1_1") (pintype "passive"))
      (node (ref "R8") (pin "1") (pinfunction "1_1") (pintype "passive"))
      (node (ref "R9") (pin "2") (pinfunction "2_2") (pintype "passive"))
      (node (ref "U$30") (pin "A1") (pinfunction "+_A1") (pintype "bidirectional"))
      (node (ref "U$48") (pin "A1") (pinfunction "+_A1") (pintype "bidirectional"))
      (node (ref "U$5") (pin "A2") (pinfunction "-_A2") (pintype "bidirectional"))
      (node (ref "U$60") (pin "A1") (pinfunction "+_A1") (pintype "bidirectional"))
      (node (ref "U$62") (pin "A1") (pinfunction "+_A1") (pintype "bidirectional"))
      (node (ref "U6") (pin "18") (pinfunction "PB0_18") (pintype "bidirectional"))
    )
    (net (code "53") (name "3.3V") (class "Default")
      (node (ref "BTN1") (pin "2") (pinfunction "2_2") (pintype "bidirectional"))
      (node (ref "C23") (pin "1") (pinfunction "1_1") (pintype "passive"))
      (node (ref "C24") (pin "1") (pinfunction "1_1") (pintype "passive"))
      (node (ref "C25") (pin "1") (pinfunction "1_1") (pintype "passive"))
      (node (ref "C26") (pin "1") (pinfunction "1_1") (pintype "passive"))
      (node (ref "IC3") (pin "5") (pinfunction "OUT_5") (pintype "bidirectional"))
      (node (ref "JP14") (pin "2") (pinfunction "2_2") (pintype "passive"))
      (node (ref "JTAG2") (pin "1") (pinfunction "1_1") (pintype "passive"))
      (node (ref "R26") (pin "1") (pinfunction "1_1") (pintype "passive"))
      (node (ref "U6") (pin "1") (pinfunction "VBAT_1") (pintype "bidirectional"))
      (node (ref "U6") (pin "24") (pinfunction "VDD_24") (pintype "bidirectional"))
      (node (ref "U6") (pin "36") (pinfunction "VDD_36") (pintype "bidirectional"))
      (node (ref "U6") (pin "40") (pinfunction "PB4/JNTRST_40") (pintype "bidirectional"))
      (node (ref "U6") (pin "48") (pinfunction "VDD_48") (pintype "bidirectional"))
      (node (ref "U6") (pin "9") (pinfunction "VDDA_9") (pintype "bidirectional"))
    )
    (net (code "54") (name "5.0V") (class "Default")
      (node (ref "C19") (pin "1") (pinfunction "1_1") (pintype "passive"))
      (node (ref "C22") (pin "1") (pinfunction "1_1") (pintype "passive"))
      (node (ref "C28") (pin "1") (pinfunction "1_1") (pintype "passive"))
      (node (ref "C31") (pin "1") (pinfunction "1_1") (pintype "passive"))
      (node (ref "CN1") (pin "VBUS") (pinfunction "VBUS_VBUS") (pintype "power_in"))
      (node (ref "IC1") (pin "3") (pinfunction "IN_3") (pintype "input"))
      (node (ref "IC3") (pin "1") (pinfunction "IN_1") (pintype "bidirectional"))
      (node (ref "IC3") (pin "3") (pinfunction "EN_3") (pintype "bidirectional"))
      (node (ref "R20") (pin "2") (pinfunction "2_2") (pintype "passive"))
      (node (ref "U7") (pin "2") (pinfunction "IN_2") (pintype "power_in"))
    )
    (net (code "55") (name "GND") (class "Default")
      (node (ref "C10") (pin "2") (pinfunction "P$2_2") (pintype "passive"))
      (node (ref "C11") (pin "2") (pinfunction "P$2_2") (pintype "passive"))
      (node (ref "C12") (pin "2") (pinfunction "P$2_2") (pintype "passive"))
      (node (ref "C13") (pin "2") (pinfunction "P$2_2") (pintype "passive"))
      (node (ref "C14") (pin "2") (pinfunction "P$2_2") (pintype "passive"))
      (node (ref "C15") (pin "2") (pinfunction "P$2_2") (pintype "passive"))
      (node (ref "C16") (pin "2") (pinfunction "P$2_2") (pintype "passive"))
      (node (ref "C17") (pin "2") (pinfunction "P$2_2") (pintype "passive"))
      (node (ref "C18") (pin "2") (pinfunction "P$2_2") (pintype "passive"))
      (node (ref "C19") (pin "2") (pinfunction "2_2") (pintype "passive"))
      (node (ref "C2") (pin "2") (pinfunction "P$2_2") (pintype "passive"))
      (node (ref "C20") (pin "1") (pinfunction "1_1") (pintype "passive"))
      (node (ref "C21") (pin "1") (pinfunction "1_1") (pintype "passive"))
      (node (ref "C22") (pin "2") (pinfunction "2_2") (pintype "passive"))
      (node (ref "C23") (pin "2") (pinfunction "2_2") (pintype "passive"))
      (node (ref "C24") (pin "2") (pinfunction "2_2") (pintype "passive"))
      (node (ref "C25") (pin "2") (pinfunction "2_2") (pintype "passive"))
      (node (ref "C26") (pin "2") (pinfunction "2_2") (pintype "passive"))
      (node (ref "C27") (pin "2") (pinfunction "2_2") (pintype "passive"))
      (node (ref "C28") (pin "2") (pinfunction "2_2") (pintype "passive"))
      (node (ref "C29") (pin "2") (pinfunction "2_2") (pintype "passive"))
      (node (ref "C3") (pin "2") (pinfunction "P$2_2") (pintype "passive"))
      (node (ref "C30") (pin "2") (pinfunction "2_2") (pintype "passive"))
      (node (ref "C31") (pin "2") (pinfunction "2_2") (pintype "passive"))
      (node (ref "C32") (pin "2") (pinfunction "2_2") (pintype "passive"))
      (node (ref "C4") (pin "2") (pinfunction "P$2_2") (pintype "passive"))
      (node (ref "C5") (pin "2") (pinfunction "P$2_2") (pintype "passive"))
      (node (ref "C6") (pin "2") (pinfunction "P$2_2") (pintype "passive"))
      (node (ref "C8") (pin "2") (pinfunction "P$2_2") (pintype "passive"))
      (node (ref "C9") (pin "2") (pinfunction "P$2_2") (pintype "passive"))
      (node (ref "CN1") (pin "GND") (pinfunction "GND_GND") (pintype "power_in"))
      (node (ref "CN1") (pin "ID") (pinfunction "ID_ID") (pintype "bidirectional"))
      (node (ref "D2") (pin "C") (pinfunction "C_C") (pintype "passive"))
      (node (ref "D3") (pin "C") (pinfunction "C_C") (pintype "passive"))
      (node (ref "D4") (pin "C") (pinfunction "C_C") (pintype "passive"))
      (node (ref "D5") (pin "C") (pinfunction "C_C") (pintype "passive"))
      (node (ref "IC1") (pin "1") (pinfunction "ADJ_1") (pintype "input"))
      (node (ref "IC3") (pin "2") (pinfunction "GND_2") (pintype "bidirectional"))
      (node (ref "JP10") (pin "1") (pinfunction "1_1") (pintype "passive"))
      (node (ref "JP11") (pin "1") (pinfunction "1_1") (pintype "passive"))
      (node (ref "JP12") (pin "1") (pinfunction "1_1") (pintype "passive"))
      (node (ref "JP4") (pin "1") (pinfunction "1_1") (pintype "passive"))
      (node (ref "JP8") (pin "1") (pinfunction "1_1") (pintype "passive"))
      (node (ref "JP9") (pin "1") (pinfunction "1_1") (pintype "passive"))
      (node (ref "JTAG1") (pin "3") (pinfunction "3_3") (pintype "passive"))
      (node (ref "JTAG1") (pin "5") (pinfunction "5_5") (pintype "passive"))
      (node (ref "JTAG2") (pin "3") (pinfunction "3_3") (pintype "passive"))
      (node (ref "JTAG2") (pin "5") (pinfunction "5_5") (pintype "passive"))
      (node (ref "R11") (pin "1") (pinfunction "1_1") (pintype "passive"))
      (node (ref "R29") (pin "1") (pinfunction "1_1") (pintype "passive"))
      (node (ref "U$2") (pin "B1") (pinfunction "GND_B1") (pintype "bidirectional"))
      (node (ref "U$30") (pin "B1") (pinfunction "GND_B1") (pintype "bidirectional"))
      (node (ref "U$48") (pin "B1") (pinfunction "GND_B1") (pintype "bidirectional"))
      (node (ref "U$5") (pin "B1") (pinfunction "GND_B1") (pintype "bidirectional"))
      (node (ref "U$60") (pin "B1") (pinfunction "GND_B1") (pintype "bidirectional"))
      (node (ref "U$62") (pin "B1") (pinfunction "GND_B1") (pintype "bidirectional"))
      (node (ref "U$99") (pin "B1") (pinfunction "GND_B1") (pintype "bidirectional"))
      (node (ref "U1") (pin "10") (pinfunction "GND1_10") (pintype "power_in"))
      (node (ref "U1") (pin "28") (pinfunction "GND2_28") (pintype "power_in"))
      (node (ref "U1") (pin "33") (pinfunction "GND_33") (pintype "power_in"))
      (node (ref "U2") (pin "18") (pinfunction "GND2_18") (pintype "power_in"))
      (node (ref "U2") (pin "5") (pinfunction "NC/GND_5") (pintype "bidirectional"))
      (node (ref "U2") (pin "PAD") (pinfunction "GND_PAD") (pintype "power_in"))
      (node (ref "U3") (pin "2") (pinfunction "GNDA_2") (pintype "bidirectional"))
      (node (ref "U3") (pin "3") (pinfunction "GNDB_3") (pintype "bidirectional"))
      (node (ref "U3") (pin "5") (pinfunction "PGND_5") (pintype "bidirectional"))
      (node (ref "U3") (pin "PAD") (pinfunction "GND_PAD_PAD") (pintype "bidirectional"))
      (node (ref "U4") (pin "14_GND") (pinfunction "GND3_14_GND") (pintype "power_in"))
      (node (ref "U4") (pin "17_GND") (pinfunction "GND4_17_GND") (pintype "power_in"))
      (node (ref "U4") (pin "21_GND") (pinfunction "GND5_21_GND") (pintype "bidirectional"))
      (node (ref "U4") (pin "24_GND") (pinfunction "GND6_24_GND") (pintype "bidirectional"))
      (node (ref "U4") (pin "26_GND") (pinfunction "GND7_26_GND") (pintype "power_in"))
      (node (ref "U4") (pin "28_GND") (pinfunction "GND8_28_GND") (pintype "power_in"))
      (node (ref "U4") (pin "2_GND") (pinfunction "GND1_2_GND") (pintype "power_in"))
      (node (ref "U4") (pin "32_VDD_USB") (pinfunction "VDD_USB_32_VDD_USB") (pintype "bidirectional"))
      (node (ref "U4") (pin "33_GND") (pinfunction "GND9_33_GND") (pintype "power_in"))
      (node (ref "U4") (pin "34_GND") (pinfunction "GND10_34_GND") (pintype "power_in"))
      (node (ref "U4") (pin "35_GND") (pinfunction "GND11_35_GND") (pintype "bidirectional"))
      (node (ref "U4") (pin "36_GND") (pinfunction "GND12_36_GND") (pintype "bidirectional"))
      (node (ref "U4") (pin "4_GND") (pinfunction "GND2_4_GND") (pintype "power_in"))
      (node (ref "U5") (pin "4") (pinfunction "VSS_4") (pintype "power_in"))
      (node (ref "U5") (pin "PAD") (pinfunction "GND_PAD_PAD") (pintype "power_in"))
      (node (ref "U6") (pin "23") (pinfunction "VSS_23") (pintype "bidirectional"))
      (node (ref "U6") (pin "35") (pinfunction "VSS_35") (pintype "bidirectional"))
      (node (ref "U6") (pin "47") (pinfunction "VSS_47") (pintype "bidirectional"))
      (node (ref "U6") (pin "8") (pinfunction "VSSA_8") (pintype "bidirectional"))
      (node (ref "U7") (pin "3") (pinfunction "GND_3") (pintype "passive"))
      (node (ref "U7") (pin "6") (pinfunction "DAP_6") (pintype "passive"))
    )
    (net (code "56") (name "Net-(C1-P$1)") (class "Default")
      (node (ref "C1") (pin "1") (pinfunction "P$1_1") (pintype "passive"))
      (node (ref "U4") (pin "3_ANT_OUT") (pinfunction "ANT_OUT_3_ANT_OUT") (pintype "output"))
    )
    (net (code "57") (name "Net-(C1-P$2)") (class "Default")
      (node (ref "C1") (pin "2") (pinfunction "P$2_2") (pintype "passive"))
      (node (ref "U4") (pin "1_ANT_IN") (pinfunction "ANT_IN_1_ANT_IN") (pintype "input"))
    )
    (net (code "58") (name "Net-(C2-P$1)") (class "Default")
      (node (ref "C2") (pin "1") (pinfunction "P$1_1") (pintype "passive"))
      (node (ref "U1") (pin "29") (pinfunction "VDD_CORE_29") (pintype "power_in"))
    )
    (net (code "59") (name "Net-(C7-P$1)") (class "Default")
      (node (ref "C7") (pin "1") (pinfunction "P$1_1") (pintype "passive"))
      (node (ref "L3") (pin "2") (pinfunction "2_2") (pintype "passive"))
    )
    (net (code "60") (name "Net-(C7-P$2)") (class "Default")
      (node (ref "C7") (pin "2") (pinfunction "P$2_2") (pintype "passive"))
      (node (ref "L2") (pin "1") (pinfunction "1_1") (pintype "passive"))
      (node (ref "U2") (pin "4") (pinfunction "TX_4") (pintype "output"))
    )
    (net (code "61") (name "Net-(C8-P$1)") (class "Default")
      (node (ref "C8") (pin "1") (pinfunction "P$1_1") (pintype "passive"))
      (node (ref "L3") (pin "1") (pinfunction "1_1") (pintype "passive"))
      (node (ref "L4") (pin "2") (pinfunction "2_2") (pintype "passive"))
    )
    (net (code "62") (name "Net-(C9-P$1)") (class "Default")
      (node (ref "C9") (pin "1") (pinfunction "P$1_1") (pintype "passive"))
      (node (ref "L4") (pin "1") (pinfunction "1_1") (pintype "passive"))
      (node (ref "L5") (pin "2") (pinfunction "2_2") (pintype "passive"))
    )
    (net (code "63") (name "Net-(C15-P$1)") (class "Default")
      (node (ref "C15") (pin "1") (pinfunction "P$1_1") (pintype "passive"))
      (node (ref "R4") (pin "1") (pinfunction "1_1") (pintype "passive"))
      (node (ref "U4") (pin "13_RX") (pinfunction "RX_13_RX") (pintype "bidirectional"))
    )
    (net (code "64") (name "Net-(CN1-PadD+)") (class "Default")
      (node (ref "CN1") (pin "D+") (pinfunction "D+_D+") (pintype "bidirectional"))
      (node (ref "R12") (pin "2") (pinfunction "2_2") (pintype "passive"))
      (node (ref "R21") (pin "2") (pinfunction "2_2") (pintype "passive"))
    )
    (net (code "65") (name "Net-(CN1-PadD-)") (class "Default")
      (node (ref "CN1") (pin "D-") (pinfunction "D-_D-") (pintype "bidirectional"))
      (node (ref "R19") (pin "2") (pinfunction "2_2") (pintype "passive"))
    )
    (net (code "66") (name "Net-(D1-PadC)") (class "Default")
      (node (ref "D1") (pin "C") (pinfunction "C_C") (pintype "passive"))
      (node (ref "R1") (pin "2") (pinfunction "2_2") (pintype "passive"))
    )
    (net (code "67") (name "Net-(D2-PadA)") (class "Default")
      (node (ref "D2") (pin "A") (pinfunction "A_A") (pintype "passive"))
      (node (ref "R25") (pin "2") (pinfunction "2_2") (pintype "passive"))
    )
    (net (code "68") (name "Net-(D3-PadA)") (class "Default")
      (node (ref "D3") (pin "A") (pinfunction "A_A") (pintype "passive"))
      (node (ref "R26") (pin "2") (pinfunction "2_2") (pintype "passive"))
    )
    (net (code "69") (name "Net-(D4-PadA)") (class "Default")
      (node (ref "D4") (pin "A") (pinfunction "A_A") (pintype "passive"))
      (node (ref "R27") (pin "2") (pinfunction "2_2") (pintype "passive"))
    )
    (net (code "70") (name "Net-(D5-PadA)") (class "Default")
      (node (ref "D5") (pin "A") (pinfunction "A_A") (pintype "passive"))
      (node (ref "R28") (pin "2") (pinfunction "2_2") (pintype "passive"))
    )
    (net (code "71") (name "Net-(U3-LX)") (class "Default")
      (node (ref "L1") (pin "1") (pinfunction "1_1") (pintype "passive"))
      (node (ref "U3") (pin "6") (pinfunction "LX_6") (pintype "bidirectional"))
    )
    (net (code "72") (name "Net-(U4-TIMEPULSE{slash}TDO)") (class "Default")
      (node (ref "R2") (pin "2") (pinfunction "2_2") (pintype "passive"))
      (node (ref "U4") (pin "23_TIMEPULSE/TDO") (pinfunction "TIMEPULSE/TDO_23_TIMEPULSE/TDO") (pintype "bidirectional"))
    )
    (net (code "73") (name "Net-(U4-TX)") (class "Default")
      (node (ref "R3") (pin "1") (pinfunction "1_1") (pintype "passive"))
      (node (ref "U4") (pin "11_TX") (pinfunction "TX_11_TX") (pintype "bidirectional"))
    )
    (net (code "74") (name "Net-(U6-BOOT0)") (class "Default")
      (node (ref "BTN1") (pin "1") (pinfunction "1_1") (pintype "bidirectional"))
      (node (ref "R29") (pin "2") (pinfunction "2_2") (pintype "passive"))
      (node (ref "U6") (pin "44") (pinfunction "BOOT0_44") (pintype "bidirectional"))
    )
    (net (code "75") (name "Net-(U6-PD0{slash}OSC_IN)") (class "Default")
      (node (ref "C20") (pin "2") (pinfunction "2_2") (pintype "passive"))
      (node (ref "U6") (pin "5") (pinfunction "PD0/OSC_IN_5") (pintype "bidirectional"))
      (node (ref "Y1") (pin "3") (pinfunction "2_3") (pintype "passive"))
    )
    (net (code "76") (name "Net-(U6-PD1{slash}OSC_OUT)") (class "Default")
      (node (ref "C21") (pin "2") (pinfunction "2_2") (pintype "passive"))
      (node (ref "U6") (pin "6") (pinfunction "PD1/OSC_OUT_6") (pintype "bidirectional"))
      (node (ref "Y1") (pin "1") (pinfunction "1_1") (pintype "passive"))
    )
    (net (code "77") (name "unconnected-(JTAG1-Pad6)") (class "Default")
      (node (ref "JTAG1") (pin "6") (pinfunction "6_6") (pintype "passive"))
    )
    (net (code "78") (name "unconnected-(JTAG1-Pad7)") (class "Default")
      (node (ref "JTAG1") (pin "7") (pinfunction "7_7") (pintype "passive"))
    )
    (net (code "79") (name "unconnected-(JTAG1-Pad8)") (class "Default")
      (node (ref "JTAG1") (pin "8") (pinfunction "8_8") (pintype "passive"))
    )
    (net (code "80") (name "unconnected-(JTAG1-Pad9)") (class "Default")
      (node (ref "JTAG1") (pin "9") (pinfunction "9_9") (pintype "passive"))
    )
    (net (code "81") (name "unconnected-(JTAG2-Pad6)") (class "Default")
      (node (ref "JTAG2") (pin "6") (pinfunction "6_6") (pintype "passive"))
    )
    (net (code "82") (name "unconnected-(JTAG2-Pad7)") (class "Default")
      (node (ref "JTAG2") (pin "7") (pinfunction "7_7") (pintype "passive"))
    )
    (net (code "83") (name "unconnected-(JTAG2-Pad8)") (class "Default")
      (node (ref "JTAG2") (pin "8") (pinfunction "8_8") (pintype "passive"))
    )
    (net (code "84") (name "unconnected-(JTAG2-Pad9)") (class "Default")
      (node (ref "JTAG2") (pin "9") (pinfunction "9_9") (pintype "passive"))
    )
    (net (code "85") (name "unconnected-(JTAG2-Pad10)") (class "Default")
      (node (ref "JTAG2") (pin "10") (pinfunction "10_10") (pintype "passive"))
    )
    (net (code "86") (name "unconnected-(U1-PA02-Pad3)") (class "Default")
      (node (ref "U1") (pin "3") (pinfunction "PA02_3") (pintype "bidirectional"))
    )
    (net (code "87") (name "unconnected-(U1-PA03-Pad4)") (class "Default")
      (node (ref "U1") (pin "4") (pinfunction "PA03_4") (pintype "bidirectional"))
    )
    (net (code "88") (name "unconnected-(U1-PA05-Pad6)") (class "Default")
      (node (ref "U1") (pin "6") (pinfunction "PA05_6") (pintype "bidirectional"))
    )
    (net (code "89") (name "unconnected-(U1-PA14-Pad15)") (class "Default")
      (node (ref "U1") (pin "15") (pinfunction "PA14_15") (pintype "bidirectional"))
    )
    (net (code "90") (name "unconnected-(U1-PA17-Pad18)") (class "Default")
      (node (ref "U1") (pin "18") (pinfunction "PA17_18") (pintype "bidirectional"))
    )
    (net (code "91") (name "unconnected-(U2-GPIO2-Pad19)") (class "Default")
      (node (ref "U2") (pin "19") (pinfunction "GPIO2_19") (pintype "bidirectional"))
    )
    (net (code "92") (name "unconnected-(U2-GPIO3-Pad20)") (class "Default")
      (node (ref "U2") (pin "20") (pinfunction "GPIO3_20") (pintype "bidirectional"))
    )
    (net (code "93") (name "unconnected-(U2-NC-Pad2)") (class "Default")
      (node (ref "U2") (pin "2") (pinfunction "NC_2") (pintype "no_connect"))
    )
    (net (code "94") (name "unconnected-(U2-NC -Pad3)") (class "Default")
      (node (ref "U2") (pin "3") (pinfunction "NC _3") (pintype "no_connect"))
    )
    (net (code "95") (name "unconnected-(U2-TXRAMP-Pad7)") (class "Default")
      (node (ref "U2") (pin "7") (pinfunction "TXRAMP_7") (pintype "bidirectional"))
    )
    (net (code "96") (name "unconnected-(U2-XOUT-Pad16)") (class "Default")
      (node (ref "U2") (pin "16") (pinfunction "XOUT_16") (pintype "output"))
    )
    (net (code "97") (name "unconnected-(U4-CFG-Pad31_CFG)") (class "Default")
      (node (ref "U4") (pin "31_CFG") (pinfunction "CFG_31_CFG") (pintype "bidirectional"))
    )
    (net (code "98") (name "unconnected-(U4-CFG_GPS0{slash}SCK-Pad9_CFG_GPS0_SCK)") (class "Default")
      (node (ref "U4") (pin "9_CFG_GPS0_SCK") (pinfunction "CFG_GPS0/SCK_9_CFG_GPS0_SCK") (pintype "bidirectional"))
    )
    (net (code "99") (name "unconnected-(U4-EXT_INTERRUPT-Pad29_EXT_INTERRUPT)") (class "Default")
      (node (ref "U4") (pin "29_EXT_INTERRUPT") (pinfunction "EXT_INTERRUPT_29_EXT_INTERRUPT") (pintype "bidirectional"))
    )
    (net (code "100") (name "unconnected-(U4-SAFEBOOT_N{slash}TDI-Pad20_SAFEBOOT_N{slash}TDI)") (class "Default")
      (node (ref "U4") (pin "20_SAFEBOOT_N/TDI") (pinfunction "SAFEBOOT_N/TDI_20_SAFEBOOT_N/TDI") (pintype "bidirectional"))
    )
    (net (code "101") (name "unconnected-(U4-SCL-Pad19_SCL)") (class "Default")
      (node (ref "U4") (pin "19_SCL") (pinfunction "SCL_19_SCL") (pintype "bidirectional"))
    )
    (net (code "102") (name "unconnected-(U4-SDA-Pad18_SDA)") (class "Default")
      (node (ref "U4") (pin "18_SDA") (pinfunction "SDA_18_SDA") (pintype "bidirectional"))
    )
    (net (code "103") (name "unconnected-(U4-SI-Pad16_SI)") (class "Default")
      (node (ref "U4") (pin "16_SI") (pinfunction "SI_16_SI") (pintype "bidirectional"))
    )
    (net (code "104") (name "unconnected-(U4-SO-Pad8_SO)") (class "Default")
      (node (ref "U4") (pin "8_SO") (pinfunction "SO_8_SO") (pintype "bidirectional"))
    )
    (net (code "105") (name "unconnected-(U4-SPI_CS-Pad10_SPI_SELECT)") (class "Default")
      (node (ref "U4") (pin "10_SPI_SELECT") (pinfunction "SPI_CS_10_SPI_SELECT") (pintype "bidirectional"))
    )
    (net (code "106") (name "unconnected-(U4-TCK-Pad22_TCK)") (class "Default")
      (node (ref "U4") (pin "22_TCK") (pinfunction "TCK_22_TCK") (pintype "bidirectional"))
    )
    (net (code "107") (name "unconnected-(U4-USB_DM-Pad7_USB_DM)") (class "Default")
      (node (ref "U4") (pin "7_USB_DM") (pinfunction "USB_DM_7_USB_DM") (pintype "bidirectional"))
    )
    (net (code "108") (name "unconnected-(U4-USB_DP-Pad6_USB_DP)") (class "Default")
      (node (ref "U4") (pin "6_USB_DP") (pinfunction "USB_DP_6_USB_DP") (pintype "bidirectional"))
    )
    (net (code "109") (name "unconnected-(U4-V_BCKP-Pad15_V_BCKUP)") (class "Default")
      (node (ref "U4") (pin "15_V_BCKUP") (pinfunction "V_BCKP_15_V_BCKUP") (pintype "bidirectional"))
    )
    (net (code "110") (name "unconnected-(U4-V_EN-Pad30_V_EN)") (class "Default")
      (node (ref "U4") (pin "30_V_EN") (pinfunction "V_EN_30_V_EN") (pintype "bidirectional"))
    )
    (net (code "111") (name "unconnected-(U4-V_TH-Pad12_V_TH)") (class "Default")
      (node (ref "U4") (pin "12_V_TH") (pinfunction "V_TH_12_V_TH") (pintype "bidirectional"))
    )
    (net (code "112") (name "unconnected-(U5-IO3{slash}RESETN-Pad7)") (class "Default")
      (node (ref "U5") (pin "7") (pinfunction "IO3/RESETN_7") (pintype "output"))
    )
    (net (code "113") (name "unconnected-(U6-NRST-Pad7)") (class "Default")
      (node (ref "U6") (pin "7") (pinfunction "NRST_7") (pintype "bidirectional"))
    )
    (net (code "114") (name "unconnected-(U6-PA9-Pad30)") (class "Default")
      (node (ref "U6") (pin "30") (pinfunction "PA9_30") (pintype "bidirectional"))
    )
    (net (code "115") (name "unconnected-(U6-PA10-Pad31)") (class "Default")
      (node (ref "U6") (pin "31") (pinfunction "PA10_31") (pintype "bidirectional"))
    )
    (net (code "116") (name "unconnected-(U6-PA15{slash}JTDI-Pad38)") (class "Default")
      (node (ref "U6") (pin "38") (pinfunction "PA15/JTDI_38") (pintype "bidirectional"))
    )
    (net (code "117") (name "unconnected-(U6-PB3{slash}JTDO-Pad39)") (class "Default")
      (node (ref "U6") (pin "39") (pinfunction "PB3/JTDO_39") (pintype "bidirectional"))
    )
    (net (code "118") (name "unconnected-(U6-PB5-Pad41)") (class "Default")
      (node (ref "U6") (pin "41") (pinfunction "PB5_41") (pintype "bidirectional"))
    )
    (net (code "119") (name "unconnected-(U6-PB6-Pad42)") (class "Default")
      (node (ref "U6") (pin "42") (pinfunction "PB6_42") (pintype "bidirectional"))
    )
    (net (code "120") (name "unconnected-(U6-PB7-Pad43)") (class "Default")
      (node (ref "U6") (pin "43") (pinfunction "PB7_43") (pintype "bidirectional"))
    )
    (net (code "121") (name "unconnected-(U6-PB8-Pad45)") (class "Default")
      (node (ref "U6") (pin "45") (pinfunction "PB8_45") (pintype "bidirectional"))
    )
    (net (code "122") (name "unconnected-(U6-PB9-Pad46)") (class "Default")
      (node (ref "U6") (pin "46") (pinfunction "PB9_46") (pintype "bidirectional"))
    )
    (net (code "123") (name "unconnected-(U6-PB12-Pad25)") (class "Default")
      (node (ref "U6") (pin "25") (pinfunction "PB12_25") (pintype "bidirectional"))
    )
    (net (code "124") (name "unconnected-(U6-PB14-Pad27)") (class "Default")
      (node (ref "U6") (pin "27") (pinfunction "PB14_27") (pintype "bidirectional"))
    )
    (net (code "125") (name "unconnected-(U6-PB15-Pad28)") (class "Default")
      (node (ref "U6") (pin "28") (pinfunction "PB15_28") (pintype "bidirectional"))
    )
    (net (code "126") (name "unconnected-(U6-PC13{slash}TAMPER_RTC-Pad2)") (class "Default")
      (node (ref "U6") (pin "2") (pinfunction "PC13/TAMPER_RTC_2") (pintype "bidirectional"))
    )
    (net (code "127") (name "unconnected-(U6-PC14{slash}OSC32_IN-Pad3)") (class "Default")
      (node (ref "U6") (pin "3") (pinfunction "PC14/OSC32_IN_3") (pintype "bidirectional"))
    )
    (net (code "128") (name "unconnected-(U6-PC15{slash}OSC32_OUT-Pad4)") (class "Default")
      (node (ref "U6") (pin "4") (pinfunction "PC15/OSC32_OUT_4") (pintype "bidirectional"))
    )
  )
)
